# controle.net
KiCad netlist of a schematic drawn in EAGLE
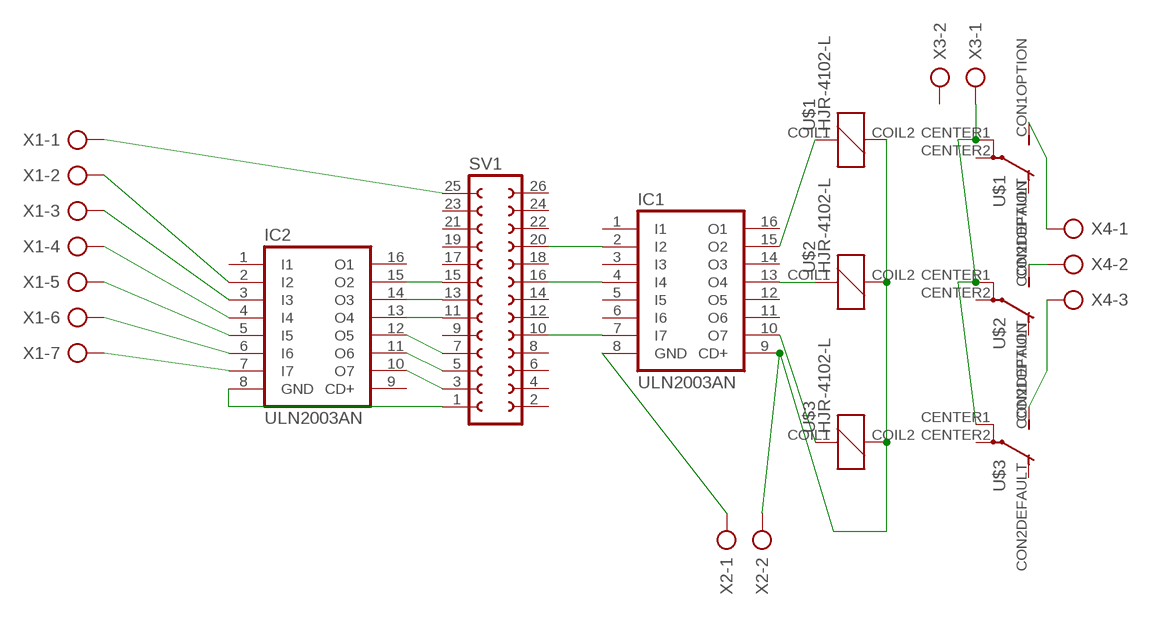
[diagram p0: schematic, sheet 1]

(export (version "E")
  (design (tool "Eeschema 10.0.6"))
  (components
    (comp (ref "IC1")
      (value "ULN2003AN")
      (footprint "eagle-import:DIL16")
      (libsource (lib "eagle-import") (part "ULN2003AN"))
    )
    (comp (ref "IC2")
      (value "ULN2003AN")
      (footprint "eagle-import:DIL16")
      (libsource (lib "eagle-import") (part "ULN2003AN"))
    )
    (comp (ref "SV1")
      (value "FE13-2")
      (footprint "eagle-import:FE13-2")
      (libsource (lib "eagle-import") (part "FE13-2"))
    )
    (comp (ref "U$1")
      (value "HJR-4102-L")
      (footprint "eagle-import:HJR4102")
      (libsource (lib "eagle-import") (part "HJR-4102-L"))
    )
    (comp (ref "U$2")
      (value "HJR-4102-L")
      (footprint "eagle-import:HJR4102")
      (libsource (lib "eagle-import") (part "HJR-4102-L"))
    )
    (comp (ref "U$3")
      (value "HJR-4102-L")
      (footprint "eagle-import:HJR4102")
      (libsource (lib "eagle-import") (part "HJR-4102-L"))
    )
    (comp (ref "X1")
      (value "AK500/7")
      (footprint "eagle-import:AK500_7")
      (libsource (lib "eagle-import") (part "AK500/7"))
    )
    (comp (ref "X2")
      (value "AK500/2")
      (footprint "eagle-import:AK500_2")
      (libsource (lib "eagle-import") (part "AK500/2"))
    )
    (comp (ref "X3")
      (value "AK500/2")
      (footprint "eagle-import:AK500_2")
      (libsource (lib "eagle-import") (part "AK500/2"))
    )
    (comp (ref "X4")
      (value "AK500/3")
      (footprint "eagle-import:AK500_3")
      (libsource (lib "eagle-import") (part "AK500/3"))
    )
  )
  (nets
    (net (code "1") (name "Net-(IC1-CD+)") (class "Default")
      (node (ref "IC1") (pin "9") (pinfunction "CD+_9") (pintype "passive"))
      (node (ref "U$1") (pin "COIL2") (pinfunction "2_COIL2") (pintype "passive"))
      (node (ref "U$2") (pin "COIL2") (pinfunction "2_COIL2") (pintype "passive"))
      (node (ref "U$3") (pin "COIL2") (pinfunction "2_COIL2") (pintype "passive"))
      (node (ref "X2") (pin "2") (pinfunction "KL_2") (pintype "passive"))
    )
    (net (code "2") (name "Net-(IC1-GND)") (class "Default")
      (node (ref "IC1") (pin "8") (pinfunction "GND_8") (pintype "power_in"))
      (node (ref "X2") (pin "1") (pinfunction "KL_1") (pintype "passive"))
    )
    (net (code "3") (name "Net-(IC1-I2)") (class "Default")
      (node (ref "IC1") (pin "2") (pinfunction "I2_2") (pintype "input"))
      (node (ref "SV1") (pin "20") (pinfunction "20_20") (pintype "passive"))
    )
    (net (code "4") (name "Net-(IC1-I4)") (class "Default")
      (node (ref "IC1") (pin "4") (pinfunction "I4_4") (pintype "input"))
      (node (ref "SV1") (pin "16") (pinfunction "16_16") (pintype "passive"))
    )
    (net (code "5") (name "Net-(IC1-I7)") (class "Default")
      (node (ref "IC1") (pin "7") (pinfunction "I7_7") (pintype "input"))
      (node (ref "SV1") (pin "10") (pinfunction "10_10") (pintype "passive"))
    )
    (net (code "6") (name "Net-(IC1-O2)") (class "Default")
      (node (ref "IC1") (pin "15") (pinfunction "O2_15") (pintype "open_collector"))
      (node (ref "U$1") (pin "COIL1") (pinfunction "1_COIL1") (pintype "passive"))
    )
    (net (code "7") (name "Net-(IC1-O4)") (class "Default")
      (node (ref "IC1") (pin "13") (pinfunction "O4_13") (pintype "open_collector"))
      (node (ref "U$2") (pin "COIL1") (pinfunction "1_COIL1") (pintype "passive"))
    )
    (net (code "8") (name "Net-(IC1-O7)") (class "Default")
      (node (ref "IC1") (pin "10") (pinfunction "O7_10") (pintype "open_collector"))
      (node (ref "U$3") (pin "COIL1") (pinfunction "1_COIL1") (pintype "passive"))
    )
    (net (code "9") (name "Net-(IC2-GND)") (class "Default")
      (node (ref "IC2") (pin "8") (pinfunction "GND_8") (pintype "power_in"))
      (node (ref "SV1") (pin "1") (pinfunction "1_1") (pintype "passive"))
    )
    (net (code "10") (name "Net-(IC2-I2)") (class "Default")
      (node (ref "IC2") (pin "2") (pinfunction "I2_2") (pintype "input"))
      (node (ref "X1") (pin "2") (pinfunction "KL_2") (pintype "passive"))
    )
    (net (code "11") (name "Net-(IC2-I3)") (class "Default")
      (node (ref "IC2") (pin "3") (pinfunction "I3_3") (pintype "input"))
      (node (ref "X1") (pin "3") (pinfunction "KL_3") (pintype "passive"))
    )
    (net (code "12") (name "Net-(IC2-I4)") (class "Default")
      (node (ref "IC2") (pin "4") (pinfunction "I4_4") (pintype "input"))
      (node (ref "X1") (pin "4") (pinfunction "KL_4") (pintype "passive"))
    )
    (net (code "13") (name "Net-(IC2-I5)") (class "Default")
      (node (ref "IC2") (pin "5") (pinfunction "I5_5") (pintype "input"))
      (node (ref "X1") (pin "5") (pinfunction "KL_5") (pintype "passive"))
    )
    (net (code "14") (name "Net-(IC2-I6)") (class "Default")
      (node (ref "IC2") (pin "6") (pinfunction "I6_6") (pintype "input"))
      (node (ref "X1") (pin "6") (pinfunction "KL_6") (pintype "passive"))
    )
    (net (code "15") (name "Net-(IC2-I7)") (class "Default")
      (node (ref "IC2") (pin "7") (pinfunction "I7_7") (pintype "input"))
      (node (ref "X1") (pin "7") (pinfunction "KL_7") (pintype "passive"))
    )
    (net (code "16") (name "Net-(IC2-O2)") (class "Default")
      (node (ref "IC2") (pin "15") (pinfunction "O2_15") (pintype "open_collector"))
      (node (ref "SV1") (pin "15") (pinfunction "15_15") (pintype "passive"))
    )
    (net (code "17") (name "Net-(IC2-O3)") (class "Default")
      (node (ref "IC2") (pin "14") (pinfunction "O3_14") (pintype "open_collector"))
      (node (ref "SV1") (pin "13") (pinfunction "13_13") (pintype "passive"))
    )
    (net (code "18") (name "Net-(IC2-O4)") (class "Default")
      (node (ref "IC2") (pin "13") (pinfunction "O4_13") (pintype "open_collector"))
      (node (ref "SV1") (pin "11") (pinfunction "11_11") (pintype "passive"))
    )
    (net (code "19") (name "Net-(IC2-O5)") (class "Default")
      (node (ref "IC2") (pin "12") (pinfunction "O5_12") (pintype "open_collector"))
      (node (ref "SV1") (pin "7") (pinfunction "7_7") (pintype "passive"))
    )
    (net (code "20") (name "Net-(IC2-O6)") (class "Default")
      (node (ref "IC2") (pin "11") (pinfunction "O6_11") (pintype "open_collector"))
      (node (ref "SV1") (pin "5") (pinfunction "5_5") (pintype "passive"))
    )
    (net (code "21") (name "Net-(IC2-O7)") (class "Default")
      (node (ref "IC2") (pin "10") (pinfunction "O7_10") (pintype "open_collector"))
      (node (ref "SV1") (pin "3") (pinfunction "3_3") (pintype "passive"))
    )
    (net (code "22") (name "Net-(U$1B-S)") (class "Default")
      (node (ref "U$1") (pin "CON1OPTION") (pinfunction "S_CON1OPTION") (pintype "passive"))
      (node (ref "X4") (pin "1") (pinfunction "KL_1") (pintype "passive"))
    )
    (net (code "23") (name "Net-(U$2B-S)") (class "Default")
      (node (ref "U$2") (pin "CON1OPTION") (pinfunction "S_CON1OPTION") (pintype "passive"))
      (node (ref "X4") (pin "2") (pinfunction "KL_2") (pintype "passive"))
    )
    (net (code "24") (name "Net-(U$3B-S)") (class "Default")
      (node (ref "U$3") (pin "CON1OPTION") (pinfunction "S_CON1OPTION") (pintype "passive"))
      (node (ref "X4") (pin "3") (pinfunction "KL_3") (pintype "passive"))
    )
    (net (code "25") (name "Net-(X1A-KL)") (class "Default")
      (node (ref "SV1") (pin "25") (pinfunction "25_25") (pintype "passive"))
      (node (ref "X1") (pin "1") (pinfunction "KL_1") (pintype "passive"))
    )
    (net (code "26") (name "Net-(X3A-KL)") (class "Default")
      (node (ref "U$1") (pin "CENTER1") (pinfunction "P_CENTER1") (pintype "passive"))
      (node (ref "U$2") (pin "CENTER1") (pinfunction "P_CENTER1") (pintype "passive"))
      (node (ref "U$3") (pin "CENTER1") (pinfunction "P_CENTER1") (pintype "passive"))
      (node (ref "X3") (pin "1") (pinfunction "KL_1") (pintype "passive"))
    )
    (net (code "27") (name "unconnected-(IC1-I1-Pad1)") (class "Default")
      (node (ref "IC1") (pin "1") (pinfunction "I1_1") (pintype "input"))
    )
    (net (code "28") (name "unconnected-(IC1-I3-Pad3)") (class "Default")
      (node (ref "IC1") (pin "3") (pinfunction "I3_3") (pintype "input"))
    )
    (net (code "29") (name "unconnected-(IC1-I5-Pad5)") (class "Default")
      (node (ref "IC1") (pin "5") (pinfunction "I5_5") (pintype "input"))
    )
    (net (code "30") (name "unconnected-(IC1-I6-Pad6)") (class "Default")
      (node (ref "IC1") (pin "6") (pinfunction "I6_6") (pintype "input"))
    )
    (net (code "31") (name "unconnected-(IC1-O1-Pad16)") (class "Default")
      (node (ref "IC1") (pin "16") (pinfunction "O1_16") (pintype "open_collector"))
    )
    (net (code "32") (name "unconnected-(IC1-O3-Pad14)") (class "Default")
      (node (ref "IC1") (pin "14") (pinfunction "O3_14") (pintype "open_collector"))
    )
    (net (code "33") (name "unconnected-(IC1-O5-Pad12)") (class "Default")
      (node (ref "IC1") (pin "12") (pinfunction "O5_12") (pintype "open_collector"))
    )
    (net (code "34") (name "unconnected-(IC1-O6-Pad11)") (class "Default")
      (node (ref "IC1") (pin "11") (pinfunction "O6_11") (pintype "open_collector"))
    )
    (net (code "35") (name "unconnected-(IC2-CD+-Pad9)") (class "Default")
      (node (ref "IC2") (pin "9") (pinfunction "CD+_9") (pintype "passive"))
    )
    (net (code "36") (name "unconnected-(IC2-I1-Pad1)") (class "Default")
      (node (ref "IC2") (pin "1") (pinfunction "I1_1") (pintype "input"))
    )
    (net (code "37") (name "unconnected-(IC2-O1-Pad16)") (class "Default")
      (node (ref "IC2") (pin "16") (pinfunction "O1_16") (pintype "open_collector"))
    )
    (net (code "38") (name "unconnected-(SV1-Pad2)") (class "Default")
      (node (ref "SV1") (pin "2") (pinfunction "2_2") (pintype "passive"))
    )
    (net (code "39") (name "unconnected-(SV1-Pad4)") (class "Default")
      (node (ref "SV1") (pin "4") (pinfunction "4_4") (pintype "passive"))
    )
    (net (code "40") (name "unconnected-(SV1-Pad6)") (class "Default")
      (node (ref "SV1") (pin "6") (pinfunction "6_6") (pintype "passive"))
    )
    (net (code "41") (name "unconnected-(SV1-Pad8)") (class "Default")
      (node (ref "SV1") (pin "8") (pinfunction "8_8") (pintype "passive"))
    )
    (net (code "42") (name "unconnected-(SV1-Pad9)") (class "Default")
      (node (ref "SV1") (pin "9") (pinfunction "9_9") (pintype "passive"))
    )
    (net (code "43") (name "unconnected-(SV1-Pad12)") (class "Default")
      (node (ref "SV1") (pin "12") (pinfunction "12_12") (pintype "passive"))
    )
    (net (code "44") (name "unconnected-(SV1-Pad14)") (class "Default")
      (node (ref "SV1") (pin "14") (pinfunction "14_14") (pintype "passive"))
    )
    (net (code "45") (name "unconnected-(SV1-Pad17)") (class "Default")
      (node (ref "SV1") (pin "17") (pinfunction "17_17") (pintype "passive"))
    )
    (net (code "46") (name "unconnected-(SV1-Pad18)") (class "Default")
      (node (ref "SV1") (pin "18") (pinfunction "18_18") (pintype "passive"))
    )
    (net (code "47") (name "unconnected-(SV1-Pad19)") (class "Default")
      (node (ref "SV1") (pin "19") (pinfunction "19_19") (pintype "passive"))
    )
    (net (code "48") (name "unconnected-(SV1-Pad21)") (class "Default")
      (node (ref "SV1") (pin "21") (pinfunction "21_21") (pintype "passive"))
    )
    (net (code "49") (name "unconnected-(SV1-Pad22)") (class "Default")
      (node (ref "SV1") (pin "22") (pinfunction "22_22") (pintype "passive"))
    )
    (net (code "50") (name "unconnected-(SV1-Pad23)") (class "Default")
      (node (ref "SV1") (pin "23") (pinfunction "23_23") (pintype "passive"))
    )
    (net (code "51") (name "unconnected-(SV1-Pad24)") (class "Default")
      (node (ref "SV1") (pin "24") (pinfunction "24_24") (pintype "passive"))
    )
    (net (code "52") (name "unconnected-(SV1-Pad26)") (class "Default")
      (node (ref "SV1") (pin "26") (pinfunction "26_26") (pintype "passive"))
    )
    (net (code "53") (name "unconnected-(U$1B-O-PadCON2DEFAULT)") (class "Default")
      (node (ref "U$1") (pin "CON2DEFAULT") (pinfunction "O_CON2DEFAULT") (pintype "passive"))
    )
    (net (code "54") (name "unconnected-(U$1B-P-PadCENTER2)") (class "Default")
      (node (ref "U$1") (pin "CENTER2") (pinfunction "P_CENTER2") (pintype "passive"))
    )
    (net (code "55") (name "unconnected-(U$2B-O-PadCON2DEFAULT)") (class "Default")
      (node (ref "U$2") (pin "CON2DEFAULT") (pinfunction "O_CON2DEFAULT") (pintype "passive"))
    )
    (net (code "56") (name "unconnected-(U$2B-P-PadCENTER2)") (class "Default")
      (node (ref "U$2") (pin "CENTER2") (pinfunction "P_CENTER2") (pintype "passive"))
    )
    (net (code "57") (name "unconnected-(U$3B-O-PadCON2DEFAULT)") (class "Default")
      (node (ref "U$3") (pin "CON2DEFAULT") (pinfunction "O_CON2DEFAULT") (pintype "passive"))
    )
    (net (code "58") (name "unconnected-(U$3B-P-PadCENTER2)") (class "Default")
      (node (ref "U$3") (pin "CENTER2") (pinfunction "P_CENTER2") (pintype "passive"))
    )
    (net (code "59") (name "unconnected-(X3B-KL-Pad2)") (class "Default")
      (node (ref "X3") (pin "2") (pinfunction "KL_2") (pintype "passive"))
    )
  )
)
